# IR_Sensor.net
KiCad netlist of a schematic drawn in Altium Designer
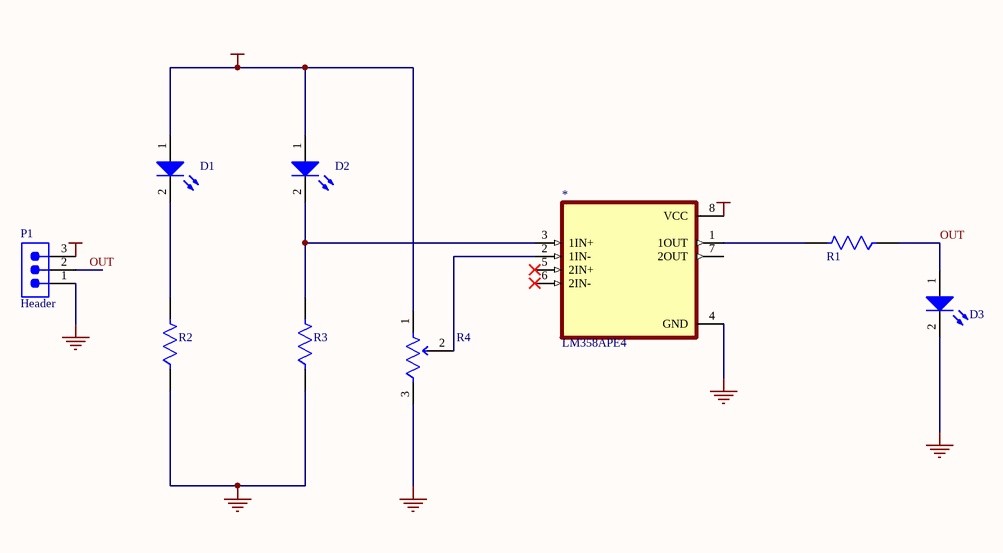
[diagram p0: IR_Sensor.SchDoc]

(export (version "E")
  (design (tool "Eeschema 10.0.6"))
  (components
    (comp (ref "*")
      (value "LM358APE4")
      (footprint "DIP794W45P254L959H508Q8")
      (description "Operational Amplifier, 2 Func, 5000uV Offset-Max, BIPolar, PDIP8")
      (fields (field (name "MANUFACTURER") "Texas Instruments"))
      (libsource (lib "Schlib") (part "LM358APE4"))
    )
    (comp (ref "D1")
      (value "151051BS04000")
      (footprint "WL-TMRC_D5.9H8.7")
      (libsource (lib "Altium Content Vault") (part "LED_Blue_1A-2K"))
    )
    (comp (ref "D2")
      (value "151051BS04000")
      (footprint "WL-TMRC_D5.9H8.7")
      (libsource (lib "Altium Content Vault") (part "LED_Blue_1A-2K"))
    )
    (comp (ref "D3")
      (value "151051BS04000")
      (footprint "WL-TMRC_D5.9H8.7")
      (libsource (lib "Altium Content Vault") (part "LED_Blue_1A-2K"))
    )
    (comp (ref "P1")
      (value "Header")
      (footprint "679303124022")
      (libsource (lib "Altium Content Vault") (part "Header_Male_1R_03P"))
    )
    (comp (ref "R1")
      (value "MRS25000C1002FCT00")
      (footprint "FP-MRS25-MFG")
      (fields (field (name "TOLERANCE") "1%"))
      (libsource (lib "Altium Content Vault") (part "1029c3af85768c4190bb7ad29bc67b5"))
    )
    (comp (ref "R2")
      (value "MRS25000C1002FCT00")
      (footprint "FP-MRS25-MFG")
      (fields (field (name "TOLERANCE") "1%"))
      (libsource (lib "Altium Content Vault") (part "1029c3af85768c4190bb7ad29bc67b5"))
    )
    (comp (ref "R3")
      (value "MRS25000C1002FCT00")
      (footprint "FP-MRS25-MFG")
      (fields (field (name "TOLERANCE") "1%"))
      (libsource (lib "Altium Content Vault") (part "1029c3af85768c4190bb7ad29bc67b5"))
    )
    (comp (ref "R4")
      (value "3386P-1-104LF")
      (footprint "FP-3386P-MFG")
      (description "TRIMMER 100K OHM 0.5W PC PIN TOP")
      (fields (field (name "TOLERANCE") "10%"))
      (libsource (lib "Altium Content Vault") (part "13357d81287629c2fd191d242cfa50c"))
    )
  )
  (nets
    (net (code "1") (name "+5") (class "Default")
      (node (ref "*") (pin "8") (pinfunction "VCC_8") (pintype "power_in"))
      (node (ref "D1") (pin "1") (pinfunction "A_1") (pintype "passive"))
      (node (ref "D2") (pin "1") (pinfunction "A_1") (pintype "passive"))
      (node (ref "P1") (pin "3") (pinfunction "3_3") (pintype "passive"))
      (node (ref "R4") (pin "1") (pinfunction "CCW_1") (pintype "passive"))
    )
    (net (code "2") (name "/OUT") (class "Default")
      (node (ref "D3") (pin "1") (pinfunction "A_1") (pintype "passive"))
      (node (ref "P1") (pin "2") (pinfunction "2_2") (pintype "passive"))
      (node (ref "R1") (pin "1") (pinfunction "1_1") (pintype "passive"))
    )
    (net (code "3") (name "GND") (class "Default")
      (node (ref "*") (pin "4") (pinfunction "GND_4") (pintype "power_in"))
      (node (ref "D3") (pin "2") (pinfunction "K_2") (pintype "passive"))
      (node (ref "P1") (pin "1") (pinfunction "1_1") (pintype "passive"))
      (node (ref "R2") (pin "1") (pinfunction "1_1") (pintype "passive"))
      (node (ref "R3") (pin "1") (pinfunction "1_1") (pintype "passive"))
      (node (ref "R4") (pin "3") (pinfunction "CW_3") (pintype "passive"))
    )
    (net (code "4") (name "Net-(*-1IN+)") (class "Default")
      (node (ref "*") (pin "3") (pinfunction "1IN+_3") (pintype "input"))
      (node (ref "D2") (pin "2") (pinfunction "K_2") (pintype "passive"))
      (node (ref "R3") (pin "2") (pinfunction "2_2") (pintype "passive"))
    )
    (net (code "5") (name "Net-(*-1IN-)") (class "Default")
      (node (ref "*") (pin "2") (pinfunction "1IN-_2") (pintype "input"))
      (node (ref "R4") (pin "2") (pinfunction "WIPER_2") (pintype "passive"))
    )
    (net (code "6") (name "Net-(*-1OUT)") (class "Default")
      (node (ref "*") (pin "1") (pinfunction "1OUT_1") (pintype "output"))
      (node (ref "R1") (pin "2") (pinfunction "2_2") (pintype "passive"))
    )
    (net (code "7") (name "Net-(D1-K)") (class "Default")
      (node (ref "D1") (pin "2") (pinfunction "K_2") (pintype "passive"))
      (node (ref "R2") (pin "2") (pinfunction "2_2") (pintype "passive"))
    )
    (net (code "8") (name "unconnected-(*-2IN+-Pad5)") (class "Default")
      (node (ref "*") (pin "5") (pinfunction "2IN+_5") (pintype "input+no_connect"))
    )
    (net (code "9") (name "unconnected-(*-2IN--Pad6)") (class "Default")
      (node (ref "*") (pin "6") (pinfunction "2IN-_6") (pintype "input+no_connect"))
    )
    (net (code "10") (name "unconnected-(*-2OUT-Pad7)") (class "Default")
      (node (ref "*") (pin "7") (pinfunction "2OUT_7") (pintype "output"))
    )
  )
)
